# MicroChu-328-V2-Final.net
KiCad netlist of a schematic drawn in EAGLE
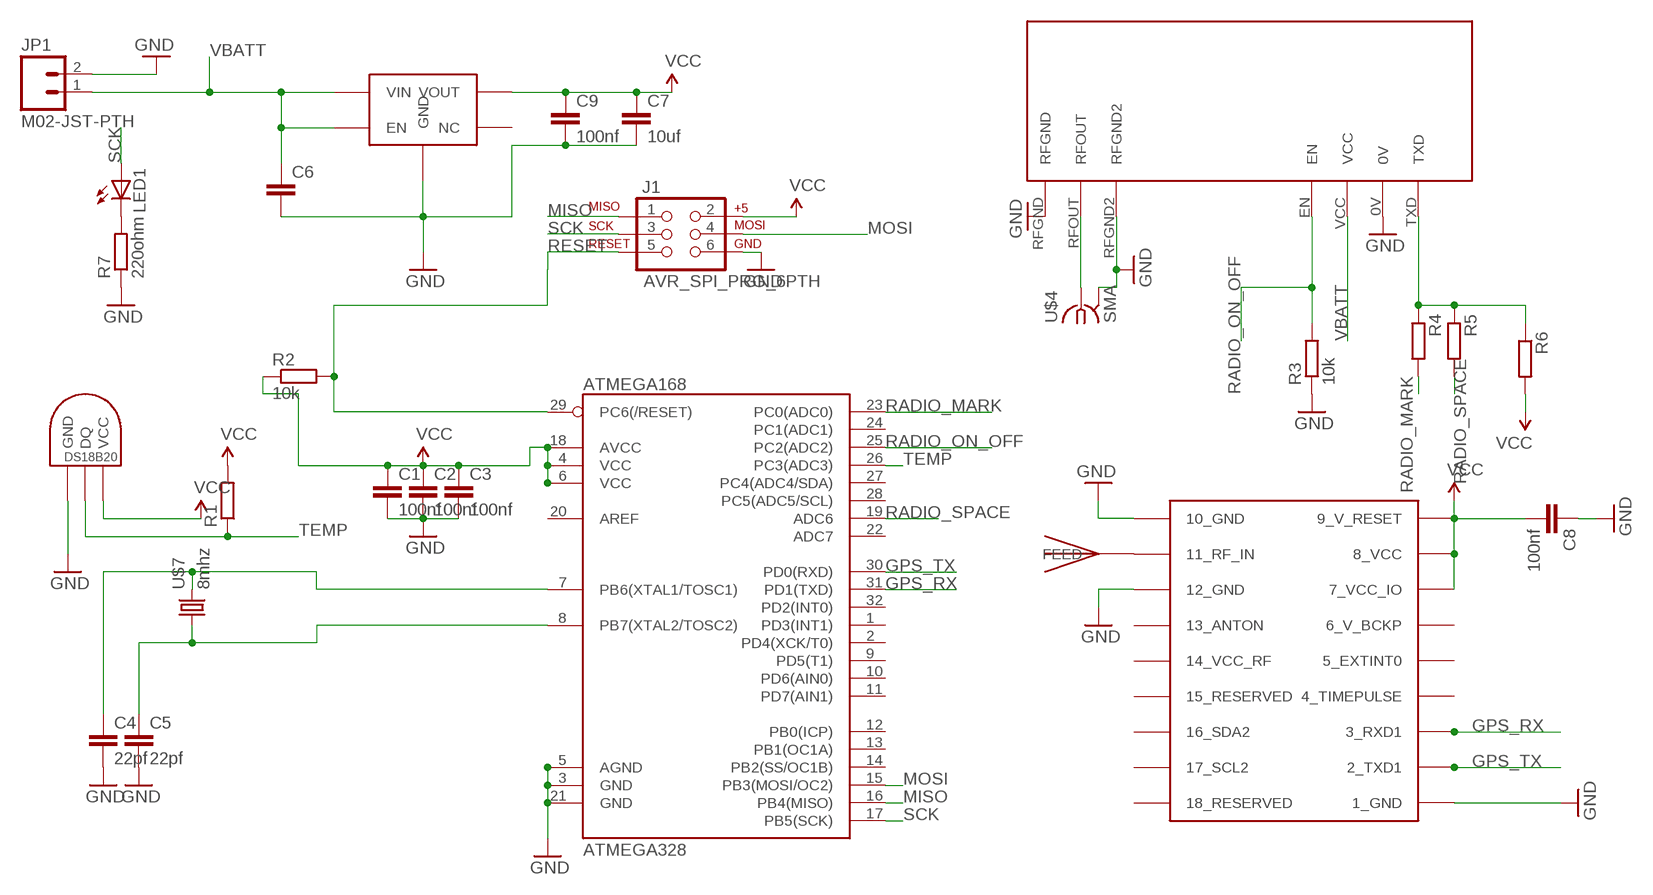
[diagram p0: schematic, sheet 1]

(export (version "E")
  (design (tool "Eeschema 10.0.6"))
  (components
    (comp (ref "3V3")
      (value "ADP122AUJZ-3V3REG-5TSOT")
      (footprint "eagle-import:SOT23-5L")
      (libsource (lib "eagle-import") (part "ADP122AUJZ-3V3REG-5TSOT"))
    )
    (comp (ref "ATMEGA328")
      (value "ATMEGA168")
      (footprint "eagle-import:TQFP32-08")
      (libsource (lib "eagle-import") (part "ATMEGA168"))
    )
    (comp (ref "C1")
      (value "100nf")
      (footprint "eagle-import:C0805")
      (libsource (lib "eagle-import") (part "C-EUC0805"))
    )
    (comp (ref "C2")
      (value "100nf")
      (footprint "eagle-import:C0805")
      (libsource (lib "eagle-import") (part "C-EUC0805"))
    )
    (comp (ref "C3")
      (value "100nf")
      (footprint "eagle-import:C0805")
      (libsource (lib "eagle-import") (part "C-EUC0805"))
    )
    (comp (ref "C4")
      (value "22pf")
      (footprint "eagle-import:C0805")
      (libsource (lib "eagle-import") (part "C-EUC0805"))
    )
    (comp (ref "C5")
      (value "22pf")
      (footprint "eagle-import:C0805")
      (libsource (lib "eagle-import") (part "C-EUC0805"))
    )
    (comp (ref "C6")
      (value "C-EUC0805")
      (footprint "eagle-import:C0805")
      (libsource (lib "eagle-import") (part "C-EUC0805"))
    )
    (comp (ref "C7")
      (value "10uf")
      (footprint "eagle-import:C0805")
      (libsource (lib "eagle-import") (part "C-EUC0805"))
    )
    (comp (ref "C8")
      (value "100nf")
      (footprint "eagle-import:C0805")
      (libsource (lib "eagle-import") (part "C-EUC0805"))
    )
    (comp (ref "C9")
      (value "100nf")
      (footprint "eagle-import:C0805")
      (libsource (lib "eagle-import") (part "C-EUC0805"))
    )
    (comp (ref "J1")
      (value "AVR_SPI_PRG_6PTH")
      (footprint "eagle-import:2X3")
      (libsource (lib "eagle-import") (part "AVR_SPI_PRG_6PTH"))
    )
    (comp (ref "JP1")
      (value "M02-JST-PTH")
      (footprint "eagle-import:M02-JST-PTH")
      (libsource (lib "eagle-import") (part "M02-JST-PTH"))
    )
    (comp (ref "LED1")
      (value "LED1206")
      (footprint "eagle-import:LED-1206")
      (libsource (lib "eagle-import") (part "LED1206"))
    )
    (comp (ref "R1")
      (value "R-EU_R0805")
      (footprint "eagle-import:R0805")
      (libsource (lib "eagle-import") (part "R-EU_R0805"))
    )
    (comp (ref "R2")
      (value "10k")
      (footprint "eagle-import:R0805")
      (libsource (lib "eagle-import") (part "R-EU_R0805"))
    )
    (comp (ref "R3")
      (value "10k")
      (footprint "eagle-import:R0805")
      (libsource (lib "eagle-import") (part "R-EU_R0805"))
    )
    (comp (ref "R4")
      (value "R-EU_R0805")
      (footprint "eagle-import:R0805")
      (libsource (lib "eagle-import") (part "R-EU_R0805"))
    )
    (comp (ref "R5")
      (value "R-EU_R0805")
      (footprint "eagle-import:R0805")
      (libsource (lib "eagle-import") (part "R-EU_R0805"))
    )
    (comp (ref "R6")
      (value "R-EU_R0805")
      (footprint "eagle-import:R0805")
      (libsource (lib "eagle-import") (part "R-EU_R0805"))
    )
    (comp (ref "R7")
      (value "220ohm")
      (footprint "eagle-import:R0805")
      (libsource (lib "eagle-import") (part "R-EU_R0805"))
    )
    (comp (ref "U$1")
      (value "JTI_ANTENNA-1575AT43A40")
      (footprint "eagle-import:JTI_ANTENNA-1575AT43A40")
      (libsource (lib "eagle-import") (part "JTI_ANTENNA-1575AT43A40"))
    )
    (comp (ref "U$2")
      (value "NTX2")
      (footprint "eagle-import:NTX2")
      (libsource (lib "eagle-import") (part "NTX2"))
    )
    (comp (ref "U$3")
      (value "UBLOX_MAX-6")
      (footprint "eagle-import:UBLOX_MAX-6")
      (libsource (lib "eagle-import") (part "UBLOX_MAX-6"))
    )
    (comp (ref "U$4")
      (value "SMA")
      (footprint "eagle-import:BU-SMA-H")
      (libsource (lib "eagle-import") (part "BU-SMA-H"))
    )
    (comp (ref "U$6")
      (value "DS1820TO92")
      (footprint "eagle-import:DS1820")
      (libsource (lib "eagle-import") (part "DS1820TO92"))
    )
    (comp (ref "U$7")
      (value "8mhz")
      (footprint "eagle-import:ABRACON_ABM3_CRYSTAL")
      (libsource (lib "eagle-import") (part "ABRACON_ABM3_CRYSTAL"))
    )
  )
  (nets
    (net (code "1") (name "/GPS_RX") (class "Default")
      (node (ref "ATMEGA328") (pin "31") (pinfunction "PD1(TXD)_31") (pintype "bidirectional"))
      (node (ref "U$3") (pin "3_RXD1") (pinfunction "3_RXD1_3_RXD1") (pintype "bidirectional"))
    )
    (net (code "2") (name "/GPS_TX") (class "Default")
      (node (ref "ATMEGA328") (pin "30") (pinfunction "PD0(RXD)_30") (pintype "bidirectional"))
      (node (ref "U$3") (pin "2_TXD1") (pinfunction "2_TXD1_2_TXD1") (pintype "bidirectional"))
    )
    (net (code "3") (name "/MISO") (class "Default")
      (node (ref "ATMEGA328") (pin "16") (pinfunction "PB4(MISO)_16") (pintype "bidirectional"))
      (node (ref "J1") (pin "1") (pinfunction "1_1") (pintype "passive"))
    )
    (net (code "4") (name "/MOSI") (class "Default")
      (node (ref "ATMEGA328") (pin "15") (pinfunction "PB3(MOSI/OC2)_15") (pintype "bidirectional"))
      (node (ref "J1") (pin "4") (pinfunction "4_4") (pintype "passive"))
    )
    (net (code "5") (name "/RADIO_MARK") (class "Default")
      (node (ref "ATMEGA328") (pin "23") (pinfunction "PC0(ADC0)_23") (pintype "bidirectional"))
      (node (ref "R4") (pin "2") (pinfunction "2_2") (pintype "passive"))
    )
    (net (code "6") (name "/RADIO_ON_OFF") (class "Default")
      (node (ref "ATMEGA328") (pin "25") (pinfunction "PC2(ADC2)_25") (pintype "bidirectional"))
      (node (ref "R3") (pin "2") (pinfunction "2_2") (pintype "passive"))
      (node (ref "U$2") (pin "EN") (pinfunction "EN_EN") (pintype "bidirectional"))
    )
    (net (code "7") (name "/RADIO_SPACE") (class "Default")
      (node (ref "ATMEGA328") (pin "19") (pinfunction "ADC6_19") (pintype "bidirectional"))
      (node (ref "R5") (pin "2") (pinfunction "2_2") (pintype "passive"))
    )
    (net (code "8") (name "/RESET") (class "Default")
      (node (ref "ATMEGA328") (pin "29") (pinfunction "PC6(/RESET)_29") (pintype "bidirectional"))
      (node (ref "J1") (pin "5") (pinfunction "5_5") (pintype "passive"))
      (node (ref "R2") (pin "2") (pinfunction "2_2") (pintype "passive"))
    )
    (net (code "9") (name "/SCK") (class "Default")
      (node (ref "ATMEGA328") (pin "17") (pinfunction "PB5(SCK)_17") (pintype "bidirectional"))
      (node (ref "J1") (pin "3") (pinfunction "3_3") (pintype "passive"))
      (node (ref "LED1") (pin "A") (pinfunction "A_A") (pintype "passive"))
    )
    (net (code "10") (name "/TEMP") (class "Default")
      (node (ref "ATMEGA328") (pin "26") (pinfunction "PC3(ADC3)_26") (pintype "bidirectional"))
      (node (ref "R1") (pin "1") (pinfunction "1_1") (pintype "passive"))
      (node (ref "U$6") (pin "DQ") (pinfunction "DQ_DQ") (pintype "bidirectional"))
    )
    (net (code "11") (name "/VBATT") (class "Default")
      (node (ref "3V3") (pin "1") (pinfunction "VIN_1") (pintype "bidirectional"))
      (node (ref "3V3") (pin "3") (pinfunction "EN_3") (pintype "bidirectional"))
      (node (ref "C6") (pin "1") (pinfunction "1_1") (pintype "passive"))
      (node (ref "JP1") (pin "1") (pinfunction "1_1") (pintype "passive"))
      (node (ref "U$2") (pin "VCC") (pinfunction "VCC_VCC") (pintype "bidirectional"))
    )
    (net (code "12") (name "GND") (class "Default")
      (node (ref "3V3") (pin "2") (pinfunction "GND_2") (pintype "bidirectional"))
      (node (ref "ATMEGA328") (pin "21") (pinfunction "GND_21") (pintype "bidirectional"))
      (node (ref "ATMEGA328") (pin "3") (pinfunction "GND_3") (pintype "bidirectional"))
      (node (ref "ATMEGA328") (pin "5") (pinfunction "AGND_5") (pintype "bidirectional"))
      (node (ref "C1") (pin "2") (pinfunction "2_2") (pintype "passive"))
      (node (ref "C2") (pin "2") (pinfunction "2_2") (pintype "passive"))
      (node (ref "C3") (pin "2") (pinfunction "2_2") (pintype "passive"))
      (node (ref "C4") (pin "2") (pinfunction "2_2") (pintype "passive"))
      (node (ref "C5") (pin "2") (pinfunction "2_2") (pintype "passive"))
      (node (ref "C6") (pin "2") (pinfunction "2_2") (pintype "passive"))
      (node (ref "C7") (pin "2") (pinfunction "2_2") (pintype "passive"))
      (node (ref "C8") (pin "1") (pinfunction "1_1") (pintype "passive"))
      (node (ref "C9") (pin "2") (pinfunction "2_2") (pintype "passive"))
      (node (ref "J1") (pin "6") (pinfunction "6_6") (pintype "passive"))
      (node (ref "JP1") (pin "2") (pinfunction "2_2") (pintype "passive"))
      (node (ref "R3") (pin "1") (pinfunction "1_1") (pintype "passive"))
      (node (ref "R7") (pin "1") (pinfunction "1_1") (pintype "passive"))
      (node (ref "U$2") (pin "0V") (pinfunction "0V_0V") (pintype "bidirectional"))
      (node (ref "U$2") (pin "RFGND") (pinfunction "RFGND_RFGND") (pintype "bidirectional"))
      (node (ref "U$2") (pin "RFGND2") (pinfunction "RFGND2_RFGND2") (pintype "bidirectional"))
      (node (ref "U$3") (pin "10_GND") (pinfunction "10_GND_10_GND") (pintype "power_in"))
      (node (ref "U$3") (pin "12_GND") (pinfunction "12_GND_12_GND") (pintype "power_in"))
      (node (ref "U$3") (pin "1_GND") (pinfunction "1_GND_1_GND") (pintype "power_in"))
      (node (ref "U$4") (pin "2") (pinfunction "GND_2") (pintype "power_in"))
      (node (ref "U$6") (pin "GND") (pinfunction "GND_GND") (pintype "power_in"))
    )
    (net (code "13") (name "Net-(ATMEGA328-PB6(XTAL1{slash}TOSC1))") (class "Default")
      (node (ref "ATMEGA328") (pin "7") (pinfunction "PB6(XTAL1/TOSC1)_7") (pintype "bidirectional"))
      (node (ref "C4") (pin "1") (pinfunction "1_1") (pintype "passive"))
      (node (ref "U$7") (pin "P$2") (pinfunction "2_P$2") (pintype "passive"))
    )
    (net (code "14") (name "Net-(ATMEGA328-PB7(XTAL2{slash}TOSC2))") (class "Default")
      (node (ref "ATMEGA328") (pin "8") (pinfunction "PB7(XTAL2/TOSC2)_8") (pintype "bidirectional"))
      (node (ref "C5") (pin "1") (pinfunction "1_1") (pintype "passive"))
      (node (ref "U$7") (pin "P$1") (pinfunction "1_P$1") (pintype "passive"))
    )
    (net (code "15") (name "Net-(LED1-PadC)") (class "Default")
      (node (ref "LED1") (pin "C") (pinfunction "C_C") (pintype "passive"))
      (node (ref "R7") (pin "2") (pinfunction "2_2") (pintype "passive"))
    )
    (net (code "16") (name "Net-(R4-Pad1)") (class "Default")
      (node (ref "R4") (pin "1") (pinfunction "1_1") (pintype "passive"))
      (node (ref "R5") (pin "1") (pinfunction "1_1") (pintype "passive"))
      (node (ref "R6") (pin "1") (pinfunction "1_1") (pintype "passive"))
      (node (ref "U$2") (pin "TXD") (pinfunction "TXD_TXD") (pintype "bidirectional"))
    )
    (net (code "17") (name "Net-(U$1-PadFEED)") (class "Default")
      (node (ref "U$1") (pin "FEED") (pinfunction "FEED_FEED") (pintype "bidirectional"))
      (node (ref "U$3") (pin "11_RF_IN") (pinfunction "11_RF_IN_11_RF_IN") (pintype "bidirectional"))
    )
    (net (code "18") (name "Net-(U$2-PadRFOUT)") (class "Default")
      (node (ref "U$2") (pin "RFOUT") (pinfunction "RFOUT_RFOUT") (pintype "bidirectional"))
      (node (ref "U$4") (pin "1") (pinfunction "1_1") (pintype "passive"))
    )
    (net (code "19") (name "VCC") (class "Default")
      (node (ref "3V3") (pin "5") (pinfunction "VOUT_5") (pintype "bidirectional"))
      (node (ref "ATMEGA328") (pin "18") (pinfunction "AVCC_18") (pintype "bidirectional"))
      (node (ref "ATMEGA328") (pin "4") (pinfunction "VCC_4") (pintype "bidirectional"))
      (node (ref "ATMEGA328") (pin "6") (pinfunction "VCC_6") (pintype "bidirectional"))
      (node (ref "C1") (pin "1") (pinfunction "1_1") (pintype "passive"))
      (node (ref "C2") (pin "1") (pinfunction "1_1") (pintype "passive"))
      (node (ref "C3") (pin "1") (pinfunction "1_1") (pintype "passive"))
      (node (ref "C7") (pin "1") (pinfunction "1_1") (pintype "passive"))
      (node (ref "C8") (pin "2") (pinfunction "2_2") (pintype "passive"))
      (node (ref "C9") (pin "1") (pinfunction "1_1") (pintype "passive"))
      (node (ref "J1") (pin "2") (pinfunction "2_2") (pintype "passive"))
      (node (ref "R1") (pin "2") (pinfunction "2_2") (pintype "passive"))
      (node (ref "R2") (pin "1") (pinfunction "1_1") (pintype "passive"))
      (node (ref "R6") (pin "2") (pinfunction "2_2") (pintype "passive"))
      (node (ref "U$3") (pin "7_VCC_IO") (pinfunction "7_VCC_IO_7_VCC_IO") (pintype "power_in"))
      (node (ref "U$3") (pin "8_VCC") (pinfunction "8_VCC_8_VCC") (pintype "power_in"))
      (node (ref "U$3") (pin "9_V_RESET") (pinfunction "9_V_RESET_9_V_RESET") (pintype "power_in"))
      (node (ref "U$6") (pin "VDD") (pinfunction "VCC_VDD") (pintype "power_in"))
    )
    (net (code "20") (name "unconnected-(3V3-NC-Pad4)") (class "Default")
      (node (ref "3V3") (pin "4") (pinfunction "NC_4") (pintype "bidirectional"))
    )
    (net (code "21") (name "unconnected-(ATMEGA328-ADC7-Pad22)") (class "Default")
      (node (ref "ATMEGA328") (pin "22") (pinfunction "ADC7_22") (pintype "bidirectional"))
    )
    (net (code "22") (name "unconnected-(ATMEGA328-AREF-Pad20)") (class "Default")
      (node (ref "ATMEGA328") (pin "20") (pinfunction "AREF_20") (pintype "bidirectional"))
    )
    (net (code "23") (name "unconnected-(ATMEGA328-PB0(ICP)-Pad12)") (class "Default")
      (node (ref "ATMEGA328") (pin "12") (pinfunction "PB0(ICP)_12") (pintype "bidirectional"))
    )
    (net (code "24") (name "unconnected-(ATMEGA328-PB1(OC1A)-Pad13)") (class "Default")
      (node (ref "ATMEGA328") (pin "13") (pinfunction "PB1(OC1A)_13") (pintype "bidirectional"))
    )
    (net (code "25") (name "unconnected-(ATMEGA328-PB2(SS{slash}OC1B)-Pad14)") (class "Default")
      (node (ref "ATMEGA328") (pin "14") (pinfunction "PB2(SS/OC1B)_14") (pintype "bidirectional"))
    )
    (net (code "26") (name "unconnected-(ATMEGA328-PC1(ADC1)-Pad24)") (class "Default")
      (node (ref "ATMEGA328") (pin "24") (pinfunction "PC1(ADC1)_24") (pintype "bidirectional"))
    )
    (net (code "27") (name "unconnected-(ATMEGA328-PC4(ADC4{slash}SDA)-Pad27)") (class "Default")
      (node (ref "ATMEGA328") (pin "27") (pinfunction "PC4(ADC4/SDA)_27") (pintype "bidirectional"))
    )
    (net (code "28") (name "unconnected-(ATMEGA328-PC5(ADC5{slash}SCL)-Pad28)") (class "Default")
      (node (ref "ATMEGA328") (pin "28") (pinfunction "PC5(ADC5/SCL)_28") (pintype "bidirectional"))
    )
    (net (code "29") (name "unconnected-(ATMEGA328-PD2(INT0)-Pad32)") (class "Default")
      (node (ref "ATMEGA328") (pin "32") (pinfunction "PD2(INT0)_32") (pintype "bidirectional"))
    )
    (net (code "30") (name "unconnected-(ATMEGA328-PD3(INT1)-Pad1)") (class "Default")
      (node (ref "ATMEGA328") (pin "1") (pinfunction "PD3(INT1)_1") (pintype "bidirectional"))
    )
    (net (code "31") (name "unconnected-(ATMEGA328-PD4(XCK{slash}T0)-Pad2)") (class "Default")
      (node (ref "ATMEGA328") (pin "2") (pinfunction "PD4(XCK/T0)_2") (pintype "bidirectional"))
    )
    (net (code "32") (name "unconnected-(ATMEGA328-PD5(T1)-Pad9)") (class "Default")
      (node (ref "ATMEGA328") (pin "9") (pinfunction "PD5(T1)_9") (pintype "bidirectional"))
    )
    (net (code "33") (name "unconnected-(ATMEGA328-PD6(AIN0)-Pad10)") (class "Default")
      (node (ref "ATMEGA328") (pin "10") (pinfunction "PD6(AIN0)_10") (pintype "bidirectional"))
    )
    (net (code "34") (name "unconnected-(ATMEGA328-PD7(AIN1)-Pad11)") (class "Default")
      (node (ref "ATMEGA328") (pin "11") (pinfunction "PD7(AIN1)_11") (pintype "bidirectional"))
    )
    (net (code "35") (name "unconnected-(U$3-Pad4_TIMEPULSE)") (class "Default")
      (node (ref "U$3") (pin "4_TIMEPULSE") (pinfunction "4_TIMEPULSE_4_TIMEPULSE") (pintype "bidirectional"))
    )
    (net (code "36") (name "unconnected-(U$3-Pad5_EXTINT0)") (class "Default")
      (node (ref "U$3") (pin "5_EXTINT0") (pinfunction "5_EXTINT0_5_EXTINT0") (pintype "bidirectional"))
    )
    (net (code "37") (name "unconnected-(U$3-Pad6_V_BCKP)") (class "Default")
      (node (ref "U$3") (pin "6_V_BCKP") (pinfunction "6_V_BCKP_6_V_BCKP") (pintype "bidirectional"))
    )
    (net (code "38") (name "unconnected-(U$3-Pad13_ANTON)") (class "Default")
      (node (ref "U$3") (pin "13_ANTON") (pinfunction "13_ANTON_13_ANTON") (pintype "bidirectional"))
    )
    (net (code "39") (name "unconnected-(U$3-Pad14_VCC_RF)") (class "Default")
      (node (ref "U$3") (pin "14_VCC_RF") (pinfunction "14_VCC_RF_14_VCC_RF") (pintype "bidirectional"))
    )
    (net (code "40") (name "unconnected-(U$3-Pad15_RESERVED)") (class "Default")
      (node (ref "U$3") (pin "15_RESERVED") (pinfunction "15_RESERVED_15_RESERVED") (pintype "bidirectional"))
    )
    (net (code "41") (name "unconnected-(U$3-Pad16_SDA2)") (class "Default")
      (node (ref "U$3") (pin "16_SDA2") (pinfunction "16_SDA2_16_SDA2") (pintype "bidirectional"))
    )
    (net (code "42") (name "unconnected-(U$3-Pad17_SCL2)") (class "Default")
      (node (ref "U$3") (pin "17_SCL2") (pinfunction "17_SCL2_17_SCL2") (pintype "bidirectional"))
    )
    (net (code "43") (name "unconnected-(U$3-Pad18_RESERVED)") (class "Default")
      (node (ref "U$3") (pin "18_RESERVED") (pinfunction "18_RESERVED_18_RESERVED") (pintype "bidirectional"))
    )
  )
)
